# Port.net
KiCad netlist of a schematic drawn in Altium Designer
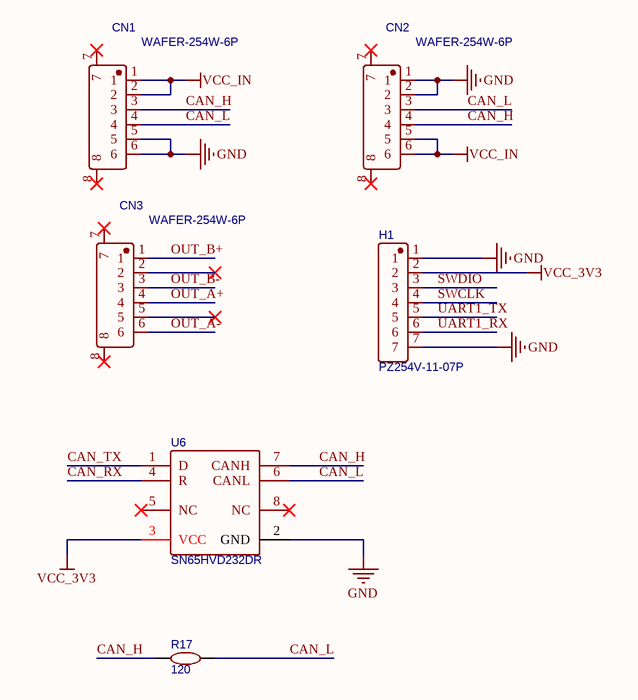
[diagram p0: Port.SchDoc]

(export (version "E")
  (design (tool "Eeschema 10.0.6"))
  (components
    (comp (ref "CN1")
      (value "WAFER-254W-6P")
      (footprint "CONN-SMD_WAFER-254W-6P")
      (fields (field (name "BOM_SUPPLIER PART") "C2856747") (field (name "CONTRIBUTOR") "LCSC"))
      (libsource (lib "6P 2.54mm") (part "WAFER-254W-6P"))
    )
    (comp (ref "CN2")
      (value "WAFER-254W-6P")
      (footprint "CONN-SMD_WAFER-254W-6P")
      (fields (field (name "BOM_SUPPLIER PART") "C2856747") (field (name "CONTRIBUTOR") "LCSC"))
      (libsource (lib "6P 2.54mm") (part "WAFER-254W-6P"))
    )
    (comp (ref "CN3")
      (value "WAFER-254W-6P")
      (footprint "CONN-SMD_WAFER-254W-6P")
      (fields (field (name "BOM_SUPPLIER PART") "C2856747") (field (name "CONTRIBUTOR") "LCSC"))
      (libsource (lib "6P 2.54mm") (part "WAFER-254W-6P"))
    )
    (comp (ref "H1")
      (value "PZ254V-11-07P")
      (footprint "HDR-TH_7P-P2.54-V-M")
      (fields (field (name "BOM_SUPPLIER PART") "C492406") (field (name "CONTRIBUTOR") "LCSC"))
      (libsource (lib "7P 2.54mm") (part "PZ254V-11-07P"))
    )
    (comp (ref "R17")
      (value "120")
      (footprint "R0603")
      (fields
        (field (name "BOM_MANUFACTURER PART") "0603WAF1200T5E")
        (field (name "BOM_SUPPLIER PART") "C22787")
      )
      (libsource (lib "120R") (part "120"))
    )
    (comp (ref "U6")
      (value "SN65HVD232DR")
      (footprint "SOIC-8_L5.0-W4.0-P1.27-LS6.0-BL")
      (fields (field (name "BOM_SUPPLIER PART") "C30530"))
      (libsource (lib "SN65HVD232DR") (part "SN65HVD232DR"))
    )
  )
  (nets
    (net (code "1") (name "/CAN_H") (class "Default")
      (node (ref "CN1") (pin "3") (pinfunction "3_3") (pintype "passive"))
      (node (ref "CN2") (pin "4") (pinfunction "4_4") (pintype "passive"))
      (node (ref "R17") (pin "1") (pinfunction "1_1") (pintype "passive"))
      (node (ref "U6") (pin "7") (pinfunction "CANH_7") (pintype "passive"))
    )
    (net (code "2") (name "/CAN_L") (class "Default")
      (node (ref "CN1") (pin "4") (pinfunction "4_4") (pintype "passive"))
      (node (ref "CN2") (pin "3") (pinfunction "3_3") (pintype "passive"))
      (node (ref "R17") (pin "2") (pinfunction "2_2") (pintype "passive"))
      (node (ref "U6") (pin "6") (pinfunction "CANL_6") (pintype "passive"))
    )
    (net (code "3") (name "/CAN_RX") (class "Default")
      (node (ref "U6") (pin "4") (pinfunction "R_4") (pintype "passive"))
    )
    (net (code "4") (name "/CAN_TX") (class "Default")
      (node (ref "U6") (pin "1") (pinfunction "D_1") (pintype "passive"))
    )
    (net (code "5") (name "/OUT_A+") (class "Default")
      (node (ref "CN3") (pin "4") (pinfunction "4_4") (pintype "passive"))
    )
    (net (code "6") (name "/OUT_A-") (class "Default")
      (node (ref "CN3") (pin "6") (pinfunction "6_6") (pintype "passive"))
    )
    (net (code "7") (name "/OUT_B+") (class "Default")
      (node (ref "CN3") (pin "1") (pinfunction "1_1") (pintype "passive"))
    )
    (net (code "8") (name "/OUT_B-") (class "Default")
      (node (ref "CN3") (pin "3") (pinfunction "3_3") (pintype "passive"))
    )
    (net (code "9") (name "/SWCLK") (class "Default")
      (node (ref "H1") (pin "4") (pinfunction "4_4") (pintype "passive"))
    )
    (net (code "10") (name "/SWDIO") (class "Default")
      (node (ref "H1") (pin "3") (pinfunction "3_3") (pintype "passive"))
    )
    (net (code "11") (name "/UART1_RX") (class "Default")
      (node (ref "H1") (pin "6") (pinfunction "6_6") (pintype "passive"))
    )
    (net (code "12") (name "/UART1_TX") (class "Default")
      (node (ref "H1") (pin "5") (pinfunction "5_5") (pintype "passive"))
    )
    (net (code "13") (name "GND") (class "Default")
      (node (ref "CN1") (pin "5") (pinfunction "5_5") (pintype "passive"))
      (node (ref "CN1") (pin "6") (pinfunction "6_6") (pintype "passive"))
      (node (ref "CN2") (pin "1") (pinfunction "1_1") (pintype "passive"))
      (node (ref "CN2") (pin "2") (pinfunction "2_2") (pintype "passive"))
      (node (ref "H1") (pin "1") (pinfunction "1_1") (pintype "passive"))
      (node (ref "H1") (pin "7") (pinfunction "7_7") (pintype "passive"))
      (node (ref "U6") (pin "2") (pinfunction "GND_2") (pintype "passive"))
    )
    (net (code "14") (name "VCC_3V3") (class "Default")
      (node (ref "H1") (pin "2") (pinfunction "2_2") (pintype "passive"))
      (node (ref "U6") (pin "3") (pinfunction "VCC_3") (pintype "passive"))
    )
    (net (code "15") (name "VCC_IN") (class "Default")
      (node (ref "CN1") (pin "1") (pinfunction "1_1") (pintype "passive"))
      (node (ref "CN1") (pin "2") (pinfunction "2_2") (pintype "passive"))
      (node (ref "CN2") (pin "5") (pinfunction "5_5") (pintype "passive"))
      (node (ref "CN2") (pin "6") (pinfunction "6_6") (pintype "passive"))
    )
    (net (code "16") (name "unconnected-(CN1-Pad7)") (class "Default")
      (node (ref "CN1") (pin "7") (pinfunction "7_7") (pintype "passive+no_connect"))
    )
    (net (code "17") (name "unconnected-(CN1-Pad8)") (class "Default")
      (node (ref "CN1") (pin "8") (pinfunction "8_8") (pintype "passive+no_connect"))
    )
    (net (code "18") (name "unconnected-(CN2-Pad7)") (class "Default")
      (node (ref "CN2") (pin "7") (pinfunction "7_7") (pintype "passive+no_connect"))
    )
    (net (code "19") (name "unconnected-(CN2-Pad8)") (class "Default")
      (node (ref "CN2") (pin "8") (pinfunction "8_8") (pintype "passive+no_connect"))
    )
    (net (code "20") (name "unconnected-(CN3-Pad2)") (class "Default")
      (node (ref "CN3") (pin "2") (pinfunction "2_2") (pintype "passive+no_connect"))
    )
    (net (code "21") (name "unconnected-(CN3-Pad5)") (class "Default")
      (node (ref "CN3") (pin "5") (pinfunction "5_5") (pintype "passive+no_connect"))
    )
    (net (code "22") (name "unconnected-(CN3-Pad7)") (class "Default")
      (node (ref "CN3") (pin "7") (pinfunction "7_7") (pintype "passive+no_connect"))
    )
    (net (code "23") (name "unconnected-(CN3-Pad8)") (class "Default")
      (node (ref "CN3") (pin "8") (pinfunction "8_8") (pintype "passive+no_connect"))
    )
    (net (code "24") (name "unconnected-(U6-NC-Pad5)") (class "Default")
      (node (ref "U6") (pin "5") (pinfunction "NC_5") (pintype "passive+no_connect"))
    )
    (net (code "25") (name "unconnected-(U6-NC-Pad8)") (class "Default")
      (node (ref "U6") (pin "8") (pinfunction "NC_8") (pintype "passive+no_connect"))
    )
  )
)
